# INA282.net
KiCad netlist of a schematic drawn in Altium Designer
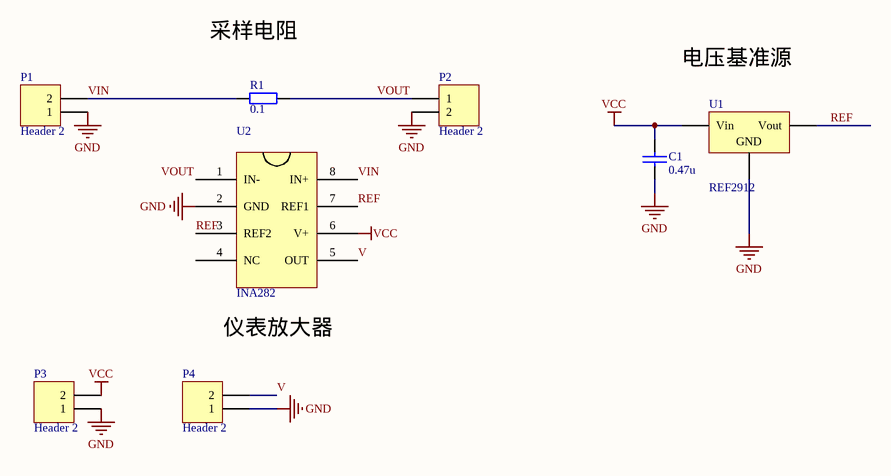
[diagram p0: INA282.SchDoc]

(export (version "E")
  (design (tool "Eeschema 10.0.6"))
  (components
    (comp (ref "C1")
      (value "0.47u")
      (footprint "0805C")
      (description "Capacitor")
      (libsource (lib "HiPCBLib") (part "CAP"))
    )
    (comp (ref "P1")
      (value "Header 2")
      (footprint "HDR1X2")
      (description "Header, 2-Pin")
      (fields (field (name "PUBLISHER") "Altium Limited"))
      (libsource (lib "") (part "Header 2_1"))
    )
    (comp (ref "P2")
      (value "Header 2")
      (footprint "HDR1X2")
      (description "Header, 2-Pin")
      (fields (field (name "PUBLISHER") "Altium Limited"))
      (libsource (lib "Miscellaneous Connectors") (part "Header 2"))
    )
    (comp (ref "P3")
      (value "Header 2")
      (footprint "HDR1X2")
      (description "Header, 2-Pin")
      (fields (field (name "PUBLISHER") "Altium Limited"))
      (libsource (lib "") (part "Header 2_1"))
    )
    (comp (ref "P4")
      (value "Header 2")
      (footprint "HDR1X2")
      (description "Header, 2-Pin")
      (fields (field (name "PUBLISHER") "Altium Limited"))
      (libsource (lib "HiPCBLib") (part "Header 2"))
    )
    (comp (ref "R1")
      (value "0.1")
      (footprint "R 2512-HP_M")
      (description "Resistor")
      (fields (field (name "Comment") "Res2") (field (name "PUBLISHER") "Altium Limited"))
      (libsource (lib "Miscellaneous Devices") (part "Res2"))
    )
    (comp (ref "U1") (value "REF2912") (footprint "LM1117") (libsource (lib "HiPCBLib") (part "AMS1117")))
    (comp (ref "U2") (value "INA282") (footprint "SO8_N") (libsource (lib "Schlib1") (part "INA282")))
  )
  (nets
    (net (code "1") (name "/REF") (class "Default")
      (node (ref "U1") (pin "2") (pinfunction "Vout_2") (pintype "passive"))
      (node (ref "U2") (pin "3") (pinfunction "REF2_3") (pintype "passive"))
      (node (ref "U2") (pin "7") (pinfunction "REF1_7") (pintype "passive"))
    )
    (net (code "2") (name "/V") (class "Default")
      (node (ref "P4") (pin "2") (pinfunction "2_2") (pintype "passive"))
      (node (ref "U2") (pin "5") (pinfunction "OUT_5") (pintype "passive"))
    )
    (net (code "3") (name "/VIN") (class "Default")
      (node (ref "P1") (pin "2") (pinfunction "2_2") (pintype "passive"))
      (node (ref "R1") (pin "2") (pinfunction "2_2") (pintype "passive"))
      (node (ref "U2") (pin "8") (pinfunction "IN+_8") (pintype "passive"))
    )
    (net (code "4") (name "/VOUT") (class "Default")
      (node (ref "P2") (pin "1") (pinfunction "1_1") (pintype "passive"))
      (node (ref "R1") (pin "1") (pinfunction "1_1") (pintype "passive"))
      (node (ref "U2") (pin "1") (pinfunction "IN-_1") (pintype "passive"))
    )
    (net (code "5") (name "GND") (class "Default")
      (node (ref "C1") (pin "1") (pinfunction "1_1") (pintype "passive"))
      (node (ref "P1") (pin "1") (pinfunction "1_1") (pintype "passive"))
      (node (ref "P2") (pin "2") (pinfunction "2_2") (pintype "passive"))
      (node (ref "P3") (pin "1") (pinfunction "1_1") (pintype "passive"))
      (node (ref "P4") (pin "1") (pinfunction "1_1") (pintype "passive"))
      (node (ref "U1") (pin "1") (pinfunction "GND_1") (pintype "passive"))
      (node (ref "U2") (pin "2") (pinfunction "GND_2") (pintype "passive"))
    )
    (net (code "6") (name "VCC") (class "Default")
      (node (ref "C1") (pin "2") (pinfunction "2_2") (pintype "passive"))
      (node (ref "P3") (pin "2") (pinfunction "2_2") (pintype "passive"))
      (node (ref "U1") (pin "3") (pinfunction "Vin_3") (pintype "passive"))
      (node (ref "U2") (pin "6") (pinfunction "V+_6") (pintype "passive"))
    )
    (net (code "7") (name "unconnected-(U2-NC-Pad4)") (class "Default")
      (node (ref "U2") (pin "4") (pinfunction "NC_4") (pintype "passive"))
    )
  )
)
